# cml_ring_osc.net
KiCad netlist of a schematic drawn in EAGLE
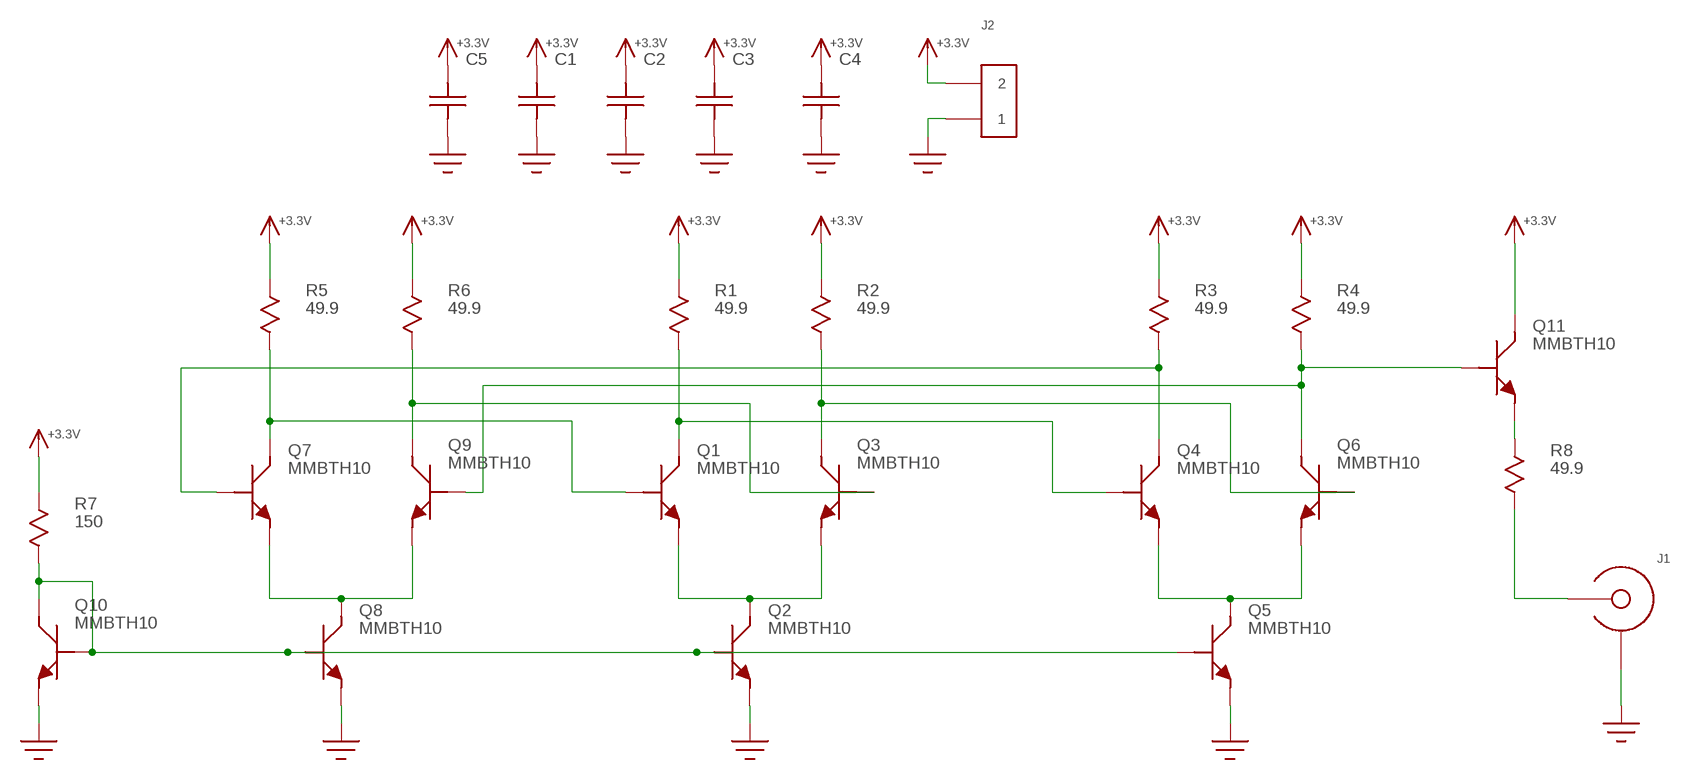
[diagram p0: schematic, sheet 1]

(export (version "E")
  (design (tool "Eeschema 10.0.6"))
  (components
    (comp (ref "C1")
      (value "C0603")
      (footprint "eagle-import:C0603")
      (libsource (lib "eagle-import") (part "C0603"))
    )
    (comp (ref "C2")
      (value "C0603")
      (footprint "eagle-import:C0603")
      (libsource (lib "eagle-import") (part "C0603"))
    )
    (comp (ref "C3")
      (value "C0603")
      (footprint "eagle-import:C0603")
      (libsource (lib "eagle-import") (part "C0603"))
    )
    (comp (ref "C4")
      (value "C0805")
      (footprint "eagle-import:0805")
      (libsource (lib "eagle-import") (part "C0805"))
    )
    (comp (ref "C5")
      (value "C0805")
      (footprint "eagle-import:0805")
      (libsource (lib "eagle-import") (part "C0805"))
    )
    (comp (ref "J1")
      (value "EDGE_LAUNCH_JACK")
      (footprint "eagle-import:EDGE_LAUNCH_RF_CON")
      (libsource (lib "eagle-import") (part "EDGE_LAUNCH_JACK"))
    )
    (comp (ref "J2")
      (value "HEADER_2PIN")
      (footprint "eagle-import:HEADER_2PIN")
      (libsource (lib "eagle-import") (part "HEADER_2PIN"))
    )
    (comp (ref "Q1")
      (value "MMBTH10")
      (footprint "eagle-import:SOT-23")
      (libsource (lib "eagle-import") (part "MMBTH10"))
    )
    (comp (ref "Q2")
      (value "MMBTH10")
      (footprint "eagle-import:SOT-23")
      (libsource (lib "eagle-import") (part "MMBTH10"))
    )
    (comp (ref "Q3")
      (value "MMBTH10")
      (footprint "eagle-import:SOT-23")
      (libsource (lib "eagle-import") (part "MMBTH10"))
    )
    (comp (ref "Q4")
      (value "MMBTH10")
      (footprint "eagle-import:SOT-23")
      (libsource (lib "eagle-import") (part "MMBTH10"))
    )
    (comp (ref "Q5")
      (value "MMBTH10")
      (footprint "eagle-import:SOT-23")
      (libsource (lib "eagle-import") (part "MMBTH10"))
    )
    (comp (ref "Q6")
      (value "MMBTH10")
      (footprint "eagle-import:SOT-23")
      (libsource (lib "eagle-import") (part "MMBTH10"))
    )
    (comp (ref "Q7")
      (value "MMBTH10")
      (footprint "eagle-import:SOT-23")
      (libsource (lib "eagle-import") (part "MMBTH10"))
    )
    (comp (ref "Q8")
      (value "MMBTH10")
      (footprint "eagle-import:SOT-23")
      (libsource (lib "eagle-import") (part "MMBTH10"))
    )
    (comp (ref "Q9")
      (value "MMBTH10")
      (footprint "eagle-import:SOT-23")
      (libsource (lib "eagle-import") (part "MMBTH10"))
    )
    (comp (ref "Q10")
      (value "MMBTH10")
      (footprint "eagle-import:SOT-23")
      (libsource (lib "eagle-import") (part "MMBTH10"))
    )
    (comp (ref "Q11")
      (value "MMBTH10")
      (footprint "eagle-import:SOT-23")
      (libsource (lib "eagle-import") (part "MMBTH10"))
    )
    (comp (ref "R1")
      (value "49.9")
      (footprint "eagle-import:R0603")
      (libsource (lib "eagle-import") (part "R0603"))
    )
    (comp (ref "R2")
      (value "49.9")
      (footprint "eagle-import:R0603")
      (libsource (lib "eagle-import") (part "R0603"))
    )
    (comp (ref "R3")
      (value "49.9")
      (footprint "eagle-import:R0603")
      (libsource (lib "eagle-import") (part "R0603"))
    )
    (comp (ref "R4")
      (value "49.9")
      (footprint "eagle-import:R0603")
      (libsource (lib "eagle-import") (part "R0603"))
    )
    (comp (ref "R5")
      (value "49.9")
      (footprint "eagle-import:R0603")
      (libsource (lib "eagle-import") (part "R0603"))
    )
    (comp (ref "R6")
      (value "49.9")
      (footprint "eagle-import:R0603")
      (libsource (lib "eagle-import") (part "R0603"))
    )
    (comp (ref "R7")
      (value "150")
      (footprint "eagle-import:R0603")
      (libsource (lib "eagle-import") (part "R0603"))
    )
    (comp (ref "R8")
      (value "49.9")
      (footprint "eagle-import:R0805")
      (libsource (lib "eagle-import") (part "R0805"))
    )
  )
  (nets
    (net (code "1") (name "+3.3V") (class "Default")
      (node (ref "C1") (pin "P$2") (pinfunction "P$2_P$2") (pintype "bidirectional"))
      (node (ref "C2") (pin "P$2") (pinfunction "P$2_P$2") (pintype "bidirectional"))
      (node (ref "C3") (pin "P$2") (pinfunction "P$2_P$2") (pintype "bidirectional"))
      (node (ref "C4") (pin "P$2") (pinfunction "P$2_P$2") (pintype "bidirectional"))
      (node (ref "C5") (pin "P$2") (pinfunction "P$2_P$2") (pintype "bidirectional"))
      (node (ref "J2") (pin "2") (pinfunction "2_2") (pintype "bidirectional"))
      (node (ref "Q11") (pin "3") (pinfunction "C_3") (pintype "bidirectional"))
      (node (ref "R1") (pin "P$1") (pinfunction "P$3_P$1") (pintype "bidirectional"))
      (node (ref "R2") (pin "P$1") (pinfunction "P$3_P$1") (pintype "bidirectional"))
      (node (ref "R3") (pin "P$1") (pinfunction "P$3_P$1") (pintype "bidirectional"))
      (node (ref "R4") (pin "P$1") (pinfunction "P$3_P$1") (pintype "bidirectional"))
      (node (ref "R5") (pin "P$1") (pinfunction "P$3_P$1") (pintype "bidirectional"))
      (node (ref "R6") (pin "P$1") (pinfunction "P$3_P$1") (pintype "bidirectional"))
      (node (ref "R7") (pin "P$1") (pinfunction "P$3_P$1") (pintype "bidirectional"))
    )
    (net (code "2") (name "GND") (class "Default")
      (node (ref "C1") (pin "P$1") (pinfunction "P$1_P$1") (pintype "bidirectional"))
      (node (ref "C2") (pin "P$1") (pinfunction "P$1_P$1") (pintype "bidirectional"))
      (node (ref "C3") (pin "P$1") (pinfunction "P$1_P$1") (pintype "bidirectional"))
      (node (ref "C4") (pin "P$1") (pinfunction "P$1_P$1") (pintype "bidirectional"))
      (node (ref "C5") (pin "P$1") (pinfunction "P$1_P$1") (pintype "bidirectional"))
      (node (ref "J1") (pin "GND@1") (pinfunction "SHIELD_GND@1") (pintype "bidirectional"))
      (node (ref "J1") (pin "GND@10") (pinfunction "SHIELD_GND@10") (pintype "bidirectional"))
      (node (ref "J1") (pin "GND@11") (pinfunction "SHIELD_GND@11") (pintype "bidirectional"))
      (node (ref "J1") (pin "GND@12") (pinfunction "SHIELD_GND@12") (pintype "bidirectional"))
      (node (ref "J1") (pin "GND@2") (pinfunction "SHIELD_GND@2") (pintype "bidirectional"))
      (node (ref "J1") (pin "GND@3") (pinfunction "SHIELD_GND@3") (pintype "bidirectional"))
      (node (ref "J1") (pin "GND@4") (pinfunction "SHIELD_GND@4") (pintype "bidirectional"))
      (node (ref "J1") (pin "GND@5") (pinfunction "SHIELD_GND@5") (pintype "bidirectional"))
      (node (ref "J1") (pin "GND@6") (pinfunction "SHIELD_GND@6") (pintype "bidirectional"))
      (node (ref "J1") (pin "GND@7") (pinfunction "SHIELD_GND@7") (pintype "bidirectional"))
      (node (ref "J1") (pin "GND@8") (pinfunction "SHIELD_GND@8") (pintype "bidirectional"))
      (node (ref "J1") (pin "GND@9") (pinfunction "SHIELD_GND@9") (pintype "bidirectional"))
      (node (ref "J1") (pin "SHIELD@1") (pinfunction "SHIELD_SHIELD@1") (pintype "bidirectional"))
      (node (ref "J1") (pin "SHIELD@2") (pinfunction "SHIELD_SHIELD@2") (pintype "bidirectional"))
      (node (ref "J2") (pin "1") (pinfunction "1_1") (pintype "bidirectional"))
      (node (ref "Q10") (pin "2") (pinfunction "E_2") (pintype "bidirectional"))
      (node (ref "Q2") (pin "2") (pinfunction "E_2") (pintype "bidirectional"))
      (node (ref "Q5") (pin "2") (pinfunction "E_2") (pintype "bidirectional"))
      (node (ref "Q8") (pin "2") (pinfunction "E_2") (pintype "bidirectional"))
    )
    (net (code "3") (name "Net-(Q1-B)") (class "Default")
      (node (ref "Q1") (pin "1") (pinfunction "B_1") (pintype "bidirectional"))
      (node (ref "Q7") (pin "3") (pinfunction "C_3") (pintype "bidirectional"))
      (node (ref "R5") (pin "P$2") (pinfunction "P$4_P$2") (pintype "bidirectional"))
    )
    (net (code "4") (name "Net-(Q1-C)") (class "Default")
      (node (ref "Q1") (pin "3") (pinfunction "C_3") (pintype "bidirectional"))
      (node (ref "Q4") (pin "1") (pinfunction "B_1") (pintype "bidirectional"))
      (node (ref "R1") (pin "P$2") (pinfunction "P$4_P$2") (pintype "bidirectional"))
    )
    (net (code "5") (name "Net-(Q1-E)") (class "Default")
      (node (ref "Q1") (pin "2") (pinfunction "E_2") (pintype "bidirectional"))
      (node (ref "Q2") (pin "3") (pinfunction "C_3") (pintype "bidirectional"))
      (node (ref "Q3") (pin "2") (pinfunction "E_2") (pintype "bidirectional"))
    )
    (net (code "6") (name "Net-(Q3-B)") (class "Default")
      (node (ref "Q3") (pin "1") (pinfunction "B_1") (pintype "bidirectional"))
      (node (ref "Q9") (pin "3") (pinfunction "C_3") (pintype "bidirectional"))
      (node (ref "R6") (pin "P$2") (pinfunction "P$4_P$2") (pintype "bidirectional"))
    )
    (net (code "7") (name "Net-(Q3-C)") (class "Default")
      (node (ref "Q3") (pin "3") (pinfunction "C_3") (pintype "bidirectional"))
      (node (ref "Q6") (pin "1") (pinfunction "B_1") (pintype "bidirectional"))
      (node (ref "R2") (pin "P$2") (pinfunction "P$4_P$2") (pintype "bidirectional"))
    )
    (net (code "8") (name "Net-(Q4-C)") (class "Default")
      (node (ref "Q4") (pin "3") (pinfunction "C_3") (pintype "bidirectional"))
      (node (ref "Q7") (pin "1") (pinfunction "B_1") (pintype "bidirectional"))
      (node (ref "R3") (pin "P$2") (pinfunction "P$4_P$2") (pintype "bidirectional"))
    )
    (net (code "9") (name "Net-(Q4-E)") (class "Default")
      (node (ref "Q4") (pin "2") (pinfunction "E_2") (pintype "bidirectional"))
      (node (ref "Q5") (pin "3") (pinfunction "C_3") (pintype "bidirectional"))
      (node (ref "Q6") (pin "2") (pinfunction "E_2") (pintype "bidirectional"))
    )
    (net (code "10") (name "Net-(Q7-E)") (class "Default")
      (node (ref "Q7") (pin "2") (pinfunction "E_2") (pintype "bidirectional"))
      (node (ref "Q8") (pin "3") (pinfunction "C_3") (pintype "bidirectional"))
      (node (ref "Q9") (pin "2") (pinfunction "E_2") (pintype "bidirectional"))
    )
    (net (code "11") (name "Net-(Q10-B)") (class "Default")
      (node (ref "Q10") (pin "1") (pinfunction "B_1") (pintype "bidirectional"))
      (node (ref "Q10") (pin "3") (pinfunction "C_3") (pintype "bidirectional"))
      (node (ref "Q2") (pin "1") (pinfunction "B_1") (pintype "bidirectional"))
      (node (ref "Q5") (pin "1") (pinfunction "B_1") (pintype "bidirectional"))
      (node (ref "Q8") (pin "1") (pinfunction "B_1") (pintype "bidirectional"))
      (node (ref "R7") (pin "P$2") (pinfunction "P$4_P$2") (pintype "bidirectional"))
    )
    (net (code "12") (name "Net-(Q11-B)") (class "Default")
      (node (ref "Q11") (pin "1") (pinfunction "B_1") (pintype "bidirectional"))
      (node (ref "Q6") (pin "3") (pinfunction "C_3") (pintype "bidirectional"))
      (node (ref "Q9") (pin "1") (pinfunction "B_1") (pintype "bidirectional"))
      (node (ref "R4") (pin "P$2") (pinfunction "P$4_P$2") (pintype "bidirectional"))
    )
    (net (code "13") (name "Net-(Q11-E)") (class "Default")
      (node (ref "Q11") (pin "2") (pinfunction "E_2") (pintype "bidirectional"))
      (node (ref "R8") (pin "P$1") (pinfunction "P$3_P$1") (pintype "bidirectional"))
    )
    (net (code "14") (name "Net-(R8-P$4)") (class "Default")
      (node (ref "J1") (pin "CENTER") (pinfunction "CENTER_CENTER") (pintype "bidirectional"))
      (node (ref "R8") (pin "P$2") (pinfunction "P$4_P$2") (pintype "bidirectional"))
    )
  )
)
